# Base_v9.net
KiCad netlist of a schematic drawn in EAGLE
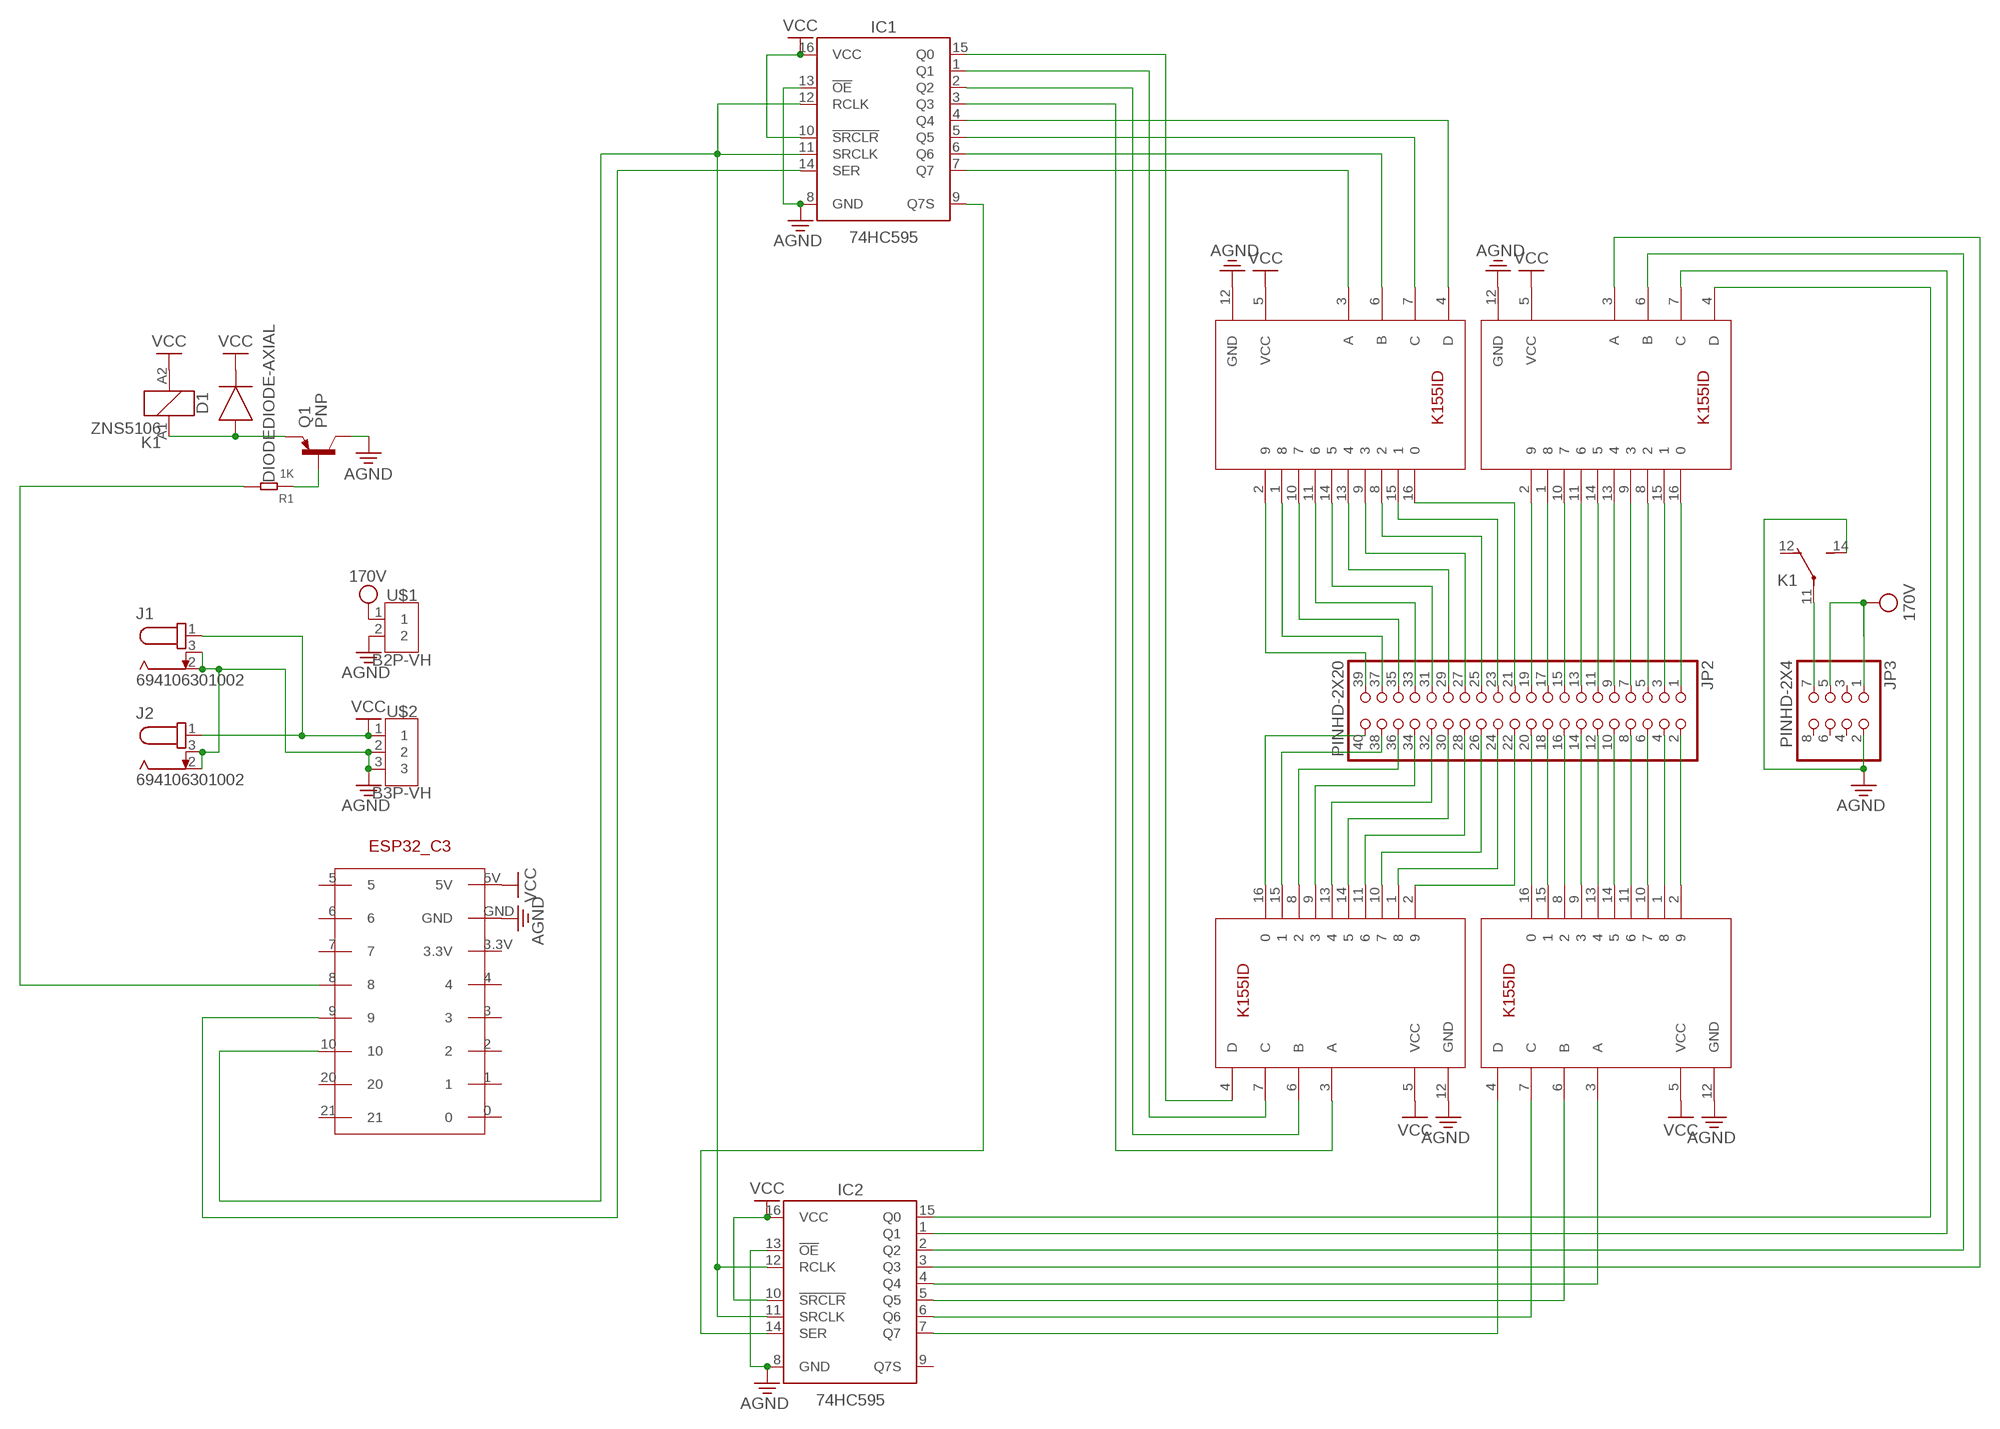
[diagram p0: schematic, sheet 1]

(export (version "E")
  (design (tool "Eeschema 10.0.6"))
  (components
    (comp (ref "D1")
      (value "DIODEDIODE-AXIAL")
      (footprint "eagle-import:DIODE-AXIAL")
      (libsource (lib "eagle-import") (part "DIODEDIODE-AXIAL"))
    )
    (comp (ref "IC1")
      (value "74HC595")
      (footprint "eagle-import:DIP762W53P254L1969H508Q16B")
      (fields (field (name "MANUFACTURER") "Generic"))
      (libsource (lib "eagle-import") (part "74HC595_PDIP"))
    )
    (comp (ref "IC2")
      (value "74HC595")
      (footprint "eagle-import:DIP762W53P254L1969H508Q16B")
      (fields (field (name "MANUFACTURER") "Generic"))
      (libsource (lib "eagle-import") (part "74HC595_PDIP"))
    )
    (comp (ref "IC3")
      (value "K155ID")
      (footprint "eagle-import:K155ID")
      (libsource (lib "eagle-import") (part "K155ID"))
    )
    (comp (ref "IC4")
      (value "K155ID")
      (footprint "eagle-import:K155ID")
      (libsource (lib "eagle-import") (part "K155ID"))
    )
    (comp (ref "IC5")
      (value "K155ID")
      (footprint "eagle-import:K155ID")
      (libsource (lib "eagle-import") (part "K155ID"))
    )
    (comp (ref "IC6")
      (value "K155ID")
      (footprint "eagle-import:K155ID")
      (libsource (lib "eagle-import") (part "K155ID"))
    )
    (comp (ref "J1")
      (value "694106301002")
      (footprint "eagle-import:694106301002")
      (fields
        (field (name "DIGIKEY_PART_NUMBER") "732-5930-ND")
        (field (name "MANUFACTURER") "Wurth Electronics Inc.")
        (field (name "CREATED_BY") "PCBLayout.com")
      )
      (libsource (lib "eagle-import") (part "694106301002"))
    )
    (comp (ref "J2")
      (value "694106301002")
      (footprint "eagle-import:694106301002")
      (fields
        (field (name "DIGIKEY_PART_NUMBER") "732-5930-ND")
        (field (name "MANUFACTURER") "Wurth Electronics Inc.")
        (field (name "CREATED_BY") "PCBLayout.com")
      )
      (libsource (lib "eagle-import") (part "694106301002"))
    )
    (comp (ref "JP2")
      (value "PINHD-2X20")
      (footprint "eagle-import:2X20")
      (fields (field (name "MANUFACTURER") "Generic"))
      (libsource (lib "eagle-import") (part "PINHD-2X20"))
    )
    (comp (ref "JP3")
      (value "PINHD-2X4")
      (footprint "eagle-import:2X04")
      (fields (field (name "MANUFACTURER") "Generic"))
      (libsource (lib "eagle-import") (part "PINHD-2X4"))
    )
    (comp (ref "K1")
      (value "ZNS5106")
      (footprint "eagle-import:ZN5")
      (libsource (lib "eagle-import") (part "ZNS5106"))
    )
    (comp (ref "Q1")
      (value "PNP")
      (footprint "eagle-import:TO92")
      (libsource (lib "eagle-import") (part "PNPTO92-CBE_"))
    )
    (comp (ref "R1")
      (value "1K")
      (footprint "eagle-import:PR-D2.3XL6.5MM")
      (fields (field (name "MPN") "FHCFR-1/4W-102J"))
      (libsource (lib "eagle-import") (part "DIP-RES-1K-5%-1/4W(PR-D2.3XL6.5MM)"))
    )
    (comp (ref "U$1")
      (value "B2P-VH")
      (footprint "eagle-import:B2P-VH_396-2N")
      (fields (field (name "MANUFACTURER") " JST Sales America Inc."))
      (libsource (lib "eagle-import") (part "B2P-VH"))
    )
    (comp (ref "U$2")
      (value "B3P-VH")
      (footprint "eagle-import:B3P-VH_396_3N")
      (fields (field (name "MANUFACTURER") " JST Sales America Inc."))
      (libsource (lib "eagle-import") (part "B3P-VH"))
    )
    (comp (ref "U$5")
      (value "ESP32_C3_SUPERMINI")
      (footprint "eagle-import:ESP32_C3_SUPERMINI")
      (libsource (lib "eagle-import") (part "ESP32_C3_SUPERMINI"))
    )
  )
  (nets
    (net (code "1") (name "170V") (class "Default")
      (node (ref "JP3") (pin "1") (pinfunction "1_1") (pintype "passive"))
      (node (ref "JP3") (pin "5") (pinfunction "5_5") (pintype "passive"))
      (node (ref "U$1") (pin "1") (pinfunction "1_1") (pintype "bidirectional"))
    )
    (net (code "2") (name "AGND") (class "Default")
      (node (ref "IC1") (pin "13") (pinfunction "~{OE}_13") (pintype "output"))
      (node (ref "IC1") (pin "8") (pinfunction "GND_8") (pintype "bidirectional"))
      (node (ref "IC2") (pin "13") (pinfunction "~{OE}_13") (pintype "output"))
      (node (ref "IC2") (pin "8") (pinfunction "GND_8") (pintype "bidirectional"))
      (node (ref "IC3") (pin "12") (pinfunction "GND_12") (pintype "bidirectional"))
      (node (ref "IC4") (pin "12") (pinfunction "GND_12") (pintype "bidirectional"))
      (node (ref "IC5") (pin "12") (pinfunction "GND_12") (pintype "bidirectional"))
      (node (ref "IC6") (pin "12") (pinfunction "GND_12") (pintype "bidirectional"))
      (node (ref "J1") (pin "2") (pinfunction "2_2") (pintype "passive"))
      (node (ref "J1") (pin "3") (pinfunction "3_3") (pintype "passive"))
      (node (ref "J2") (pin "2") (pinfunction "2_2") (pintype "passive"))
      (node (ref "J2") (pin "3") (pinfunction "3_3") (pintype "passive"))
      (node (ref "JP3") (pin "2") (pinfunction "2_2") (pintype "passive"))
      (node (ref "K1") (pin "14") (pinfunction "S_14") (pintype "passive"))
      (node (ref "Q1") (pin "1") (pinfunction "C_1") (pintype "passive"))
      (node (ref "U$1") (pin "2") (pinfunction "2_2") (pintype "bidirectional"))
      (node (ref "U$2") (pin "2") (pinfunction "2_2") (pintype "bidirectional"))
      (node (ref "U$2") (pin "3") (pinfunction "3_3") (pintype "bidirectional"))
      (node (ref "U$5") (pin "GND") (pinfunction "GND_GND") (pintype "bidirectional"))
    )
    (net (code "3") (name "Net-(D1-A)") (class "Default")
      (node (ref "D1") (pin "1") (pinfunction "A_1") (pintype "passive"))
      (node (ref "K1") (pin "A1") (pinfunction "1_A1") (pintype "passive"))
      (node (ref "Q1") (pin "3") (pinfunction "E_3") (pintype "passive"))
    )
    (net (code "4") (name "Net-(IC1-Q0)") (class "Default")
      (node (ref "IC1") (pin "15") (pinfunction "Q0_15") (pintype "output"))
      (node (ref "IC4") (pin "4") (pinfunction "D_4") (pintype "bidirectional"))
    )
    (net (code "5") (name "Net-(IC1-Q1)") (class "Default")
      (node (ref "IC1") (pin "1") (pinfunction "Q1_1") (pintype "output"))
      (node (ref "IC4") (pin "7") (pinfunction "C_7") (pintype "bidirectional"))
    )
    (net (code "6") (name "Net-(IC1-Q2)") (class "Default")
      (node (ref "IC1") (pin "2") (pinfunction "Q2_2") (pintype "output"))
      (node (ref "IC4") (pin "6") (pinfunction "B_6") (pintype "bidirectional"))
    )
    (net (code "7") (name "Net-(IC1-Q3)") (class "Default")
      (node (ref "IC1") (pin "3") (pinfunction "Q3_3") (pintype "output"))
      (node (ref "IC4") (pin "3") (pinfunction "A_3") (pintype "bidirectional"))
    )
    (net (code "8") (name "Net-(IC1-Q4)") (class "Default")
      (node (ref "IC1") (pin "4") (pinfunction "Q4_4") (pintype "output"))
      (node (ref "IC3") (pin "4") (pinfunction "D_4") (pintype "bidirectional"))
    )
    (net (code "9") (name "Net-(IC1-Q5)") (class "Default")
      (node (ref "IC1") (pin "5") (pinfunction "Q5_5") (pintype "output"))
      (node (ref "IC3") (pin "7") (pinfunction "C_7") (pintype "bidirectional"))
    )
    (net (code "10") (name "Net-(IC1-Q6)") (class "Default")
      (node (ref "IC1") (pin "6") (pinfunction "Q6_6") (pintype "output"))
      (node (ref "IC3") (pin "6") (pinfunction "B_6") (pintype "bidirectional"))
    )
    (net (code "11") (name "Net-(IC1-Q7)") (class "Default")
      (node (ref "IC1") (pin "7") (pinfunction "Q7_7") (pintype "output"))
      (node (ref "IC3") (pin "3") (pinfunction "A_3") (pintype "bidirectional"))
    )
    (net (code "12") (name "Net-(IC1-Q7S)") (class "Default")
      (node (ref "IC1") (pin "9") (pinfunction "Q7S_9") (pintype "output"))
      (node (ref "IC2") (pin "14") (pinfunction "SER_14") (pintype "input"))
    )
    (net (code "13") (name "Net-(IC1-RCLK)") (class "Default")
      (node (ref "IC1") (pin "11") (pinfunction "SRCLK_11") (pintype "input"))
      (node (ref "IC1") (pin "12") (pinfunction "RCLK_12") (pintype "input"))
      (node (ref "IC2") (pin "11") (pinfunction "SRCLK_11") (pintype "input"))
      (node (ref "IC2") (pin "12") (pinfunction "RCLK_12") (pintype "input"))
      (node (ref "U$5") (pin "10") (pinfunction "10_10") (pintype "bidirectional"))
    )
    (net (code "14") (name "Net-(IC1-SER)") (class "Default")
      (node (ref "IC1") (pin "14") (pinfunction "SER_14") (pintype "input"))
      (node (ref "U$5") (pin "9") (pinfunction "9_9") (pintype "bidirectional"))
    )
    (net (code "15") (name "Net-(IC2-Q0)") (class "Default")
      (node (ref "IC2") (pin "15") (pinfunction "Q0_15") (pintype "output"))
      (node (ref "IC5") (pin "4") (pinfunction "D_4") (pintype "bidirectional"))
    )
    (net (code "16") (name "Net-(IC2-Q1)") (class "Default")
      (node (ref "IC2") (pin "1") (pinfunction "Q1_1") (pintype "output"))
      (node (ref "IC5") (pin "7") (pinfunction "C_7") (pintype "bidirectional"))
    )
    (net (code "17") (name "Net-(IC2-Q2)") (class "Default")
      (node (ref "IC2") (pin "2") (pinfunction "Q2_2") (pintype "output"))
      (node (ref "IC5") (pin "6") (pinfunction "B_6") (pintype "bidirectional"))
    )
    (net (code "18") (name "Net-(IC2-Q3)") (class "Default")
      (node (ref "IC2") (pin "3") (pinfunction "Q3_3") (pintype "output"))
      (node (ref "IC5") (pin "3") (pinfunction "A_3") (pintype "bidirectional"))
    )
    (net (code "19") (name "Net-(IC2-Q4)") (class "Default")
      (node (ref "IC2") (pin "4") (pinfunction "Q4_4") (pintype "output"))
      (node (ref "IC6") (pin "3") (pinfunction "A_3") (pintype "bidirectional"))
    )
    (net (code "20") (name "Net-(IC2-Q5)") (class "Default")
      (node (ref "IC2") (pin "5") (pinfunction "Q5_5") (pintype "output"))
      (node (ref "IC6") (pin "6") (pinfunction "B_6") (pintype "bidirectional"))
    )
    (net (code "21") (name "Net-(IC2-Q6)") (class "Default")
      (node (ref "IC2") (pin "6") (pinfunction "Q6_6") (pintype "output"))
      (node (ref "IC6") (pin "7") (pinfunction "C_7") (pintype "bidirectional"))
    )
    (net (code "22") (name "Net-(IC2-Q7)") (class "Default")
      (node (ref "IC2") (pin "7") (pinfunction "Q7_7") (pintype "output"))
      (node (ref "IC6") (pin "4") (pinfunction "D_4") (pintype "bidirectional"))
    )
    (net (code "23") (name "Net-(IC3-0)") (class "Default")
      (node (ref "IC3") (pin "16") (pinfunction "0_16") (pintype "bidirectional"))
      (node (ref "JP2") (pin "21") (pinfunction "21_21") (pintype "passive"))
    )
    (net (code "24") (name "Net-(IC3-1)") (class "Default")
      (node (ref "IC3") (pin "15") (pinfunction "1_15") (pintype "bidirectional"))
      (node (ref "JP2") (pin "23") (pinfunction "23_23") (pintype "passive"))
    )
    (net (code "25") (name "Net-(IC3-2)") (class "Default")
      (node (ref "IC3") (pin "8") (pinfunction "2_8") (pintype "bidirectional"))
      (node (ref "JP2") (pin "25") (pinfunction "25_25") (pintype "passive"))
    )
    (net (code "26") (name "Net-(IC3-3)") (class "Default")
      (node (ref "IC3") (pin "9") (pinfunction "3_9") (pintype "bidirectional"))
      (node (ref "JP2") (pin "27") (pinfunction "27_27") (pintype "passive"))
    )
    (net (code "27") (name "Net-(IC3-4)") (class "Default")
      (node (ref "IC3") (pin "13") (pinfunction "4_13") (pintype "bidirectional"))
      (node (ref "JP2") (pin "29") (pinfunction "29_29") (pintype "passive"))
    )
    (net (code "28") (name "Net-(IC3-5)") (class "Default")
      (node (ref "IC3") (pin "14") (pinfunction "5_14") (pintype "bidirectional"))
      (node (ref "JP2") (pin "31") (pinfunction "31_31") (pintype "passive"))
    )
    (net (code "29") (name "Net-(IC3-6)") (class "Default")
      (node (ref "IC3") (pin "11") (pinfunction "6_11") (pintype "bidirectional"))
      (node (ref "JP2") (pin "33") (pinfunction "33_33") (pintype "passive"))
    )
    (net (code "30") (name "Net-(IC3-7)") (class "Default")
      (node (ref "IC3") (pin "10") (pinfunction "7_10") (pintype "bidirectional"))
      (node (ref "JP2") (pin "35") (pinfunction "35_35") (pintype "passive"))
    )
    (net (code "31") (name "Net-(IC3-8)") (class "Default")
      (node (ref "IC3") (pin "1") (pinfunction "8_1") (pintype "bidirectional"))
      (node (ref "JP2") (pin "37") (pinfunction "37_37") (pintype "passive"))
    )
    (net (code "32") (name "Net-(IC3-9)") (class "Default")
      (node (ref "IC3") (pin "2") (pinfunction "9_2") (pintype "bidirectional"))
      (node (ref "JP2") (pin "39") (pinfunction "39_39") (pintype "passive"))
    )
    (net (code "33") (name "Net-(IC4-0)") (class "Default")
      (node (ref "IC4") (pin "16") (pinfunction "0_16") (pintype "bidirectional"))
      (node (ref "JP2") (pin "40") (pinfunction "40_40") (pintype "passive"))
    )
    (net (code "34") (name "Net-(IC4-1)") (class "Default")
      (node (ref "IC4") (pin "15") (pinfunction "1_15") (pintype "bidirectional"))
      (node (ref "JP2") (pin "38") (pinfunction "38_38") (pintype "passive"))
    )
    (net (code "35") (name "Net-(IC4-2)") (class "Default")
      (node (ref "IC4") (pin "8") (pinfunction "2_8") (pintype "bidirectional"))
      (node (ref "JP2") (pin "36") (pinfunction "36_36") (pintype "passive"))
    )
    (net (code "36") (name "Net-(IC4-3)") (class "Default")
      (node (ref "IC4") (pin "9") (pinfunction "3_9") (pintype "bidirectional"))
      (node (ref "JP2") (pin "34") (pinfunction "34_34") (pintype "passive"))
    )
    (net (code "37") (name "Net-(IC4-4)") (class "Default")
      (node (ref "IC4") (pin "13") (pinfunction "4_13") (pintype "bidirectional"))
      (node (ref "JP2") (pin "32") (pinfunction "32_32") (pintype "passive"))
    )
    (net (code "38") (name "Net-(IC4-5)") (class "Default")
      (node (ref "IC4") (pin "14") (pinfunction "5_14") (pintype "bidirectional"))
      (node (ref "JP2") (pin "30") (pinfunction "30_30") (pintype "passive"))
    )
    (net (code "39") (name "Net-(IC4-6)") (class "Default")
      (node (ref "IC4") (pin "11") (pinfunction "6_11") (pintype "bidirectional"))
      (node (ref "JP2") (pin "28") (pinfunction "28_28") (pintype "passive"))
    )
    (net (code "40") (name "Net-(IC4-7)") (class "Default")
      (node (ref "IC4") (pin "10") (pinfunction "7_10") (pintype "bidirectional"))
      (node (ref "JP2") (pin "26") (pinfunction "26_26") (pintype "passive"))
    )
    (net (code "41") (name "Net-(IC4-8)") (class "Default")
      (node (ref "IC4") (pin "1") (pinfunction "8_1") (pintype "bidirectional"))
      (node (ref "JP2") (pin "24") (pinfunction "24_24") (pintype "passive"))
    )
    (net (code "42") (name "Net-(IC4-9)") (class "Default")
      (node (ref "IC4") (pin "2") (pinfunction "9_2") (pintype "bidirectional"))
      (node (ref "JP2") (pin "22") (pinfunction "22_22") (pintype "passive"))
    )
    (net (code "43") (name "Net-(IC5-0)") (class "Default")
      (node (ref "IC5") (pin "16") (pinfunction "0_16") (pintype "bidirectional"))
      (node (ref "JP2") (pin "1") (pinfunction "1_1") (pintype "passive"))
    )
    (net (code "44") (name "Net-(IC5-1)") (class "Default")
      (node (ref "IC5") (pin "15") (pinfunction "1_15") (pintype "bidirectional"))
      (node (ref "JP2") (pin "3") (pinfunction "3_3") (pintype "passive"))
    )
    (net (code "45") (name "Net-(IC5-2)") (class "Default")
      (node (ref "IC5") (pin "8") (pinfunction "2_8") (pintype "bidirectional"))
      (node (ref "JP2") (pin "5") (pinfunction "5_5") (pintype "passive"))
    )
    (net (code "46") (name "Net-(IC5-3)") (class "Default")
      (node (ref "IC5") (pin "9") (pinfunction "3_9") (pintype "bidirectional"))
      (node (ref "JP2") (pin "7") (pinfunction "7_7") (pintype "passive"))
    )
    (net (code "47") (name "Net-(IC5-4)") (class "Default")
      (node (ref "IC5") (pin "13") (pinfunction "4_13") (pintype "bidirectional"))
      (node (ref "JP2") (pin "9") (pinfunction "9_9") (pintype "passive"))
    )
    (net (code "48") (name "Net-(IC5-5)") (class "Default")
      (node (ref "IC5") (pin "14") (pinfunction "5_14") (pintype "bidirectional"))
      (node (ref "JP2") (pin "11") (pinfunction "11_11") (pintype "passive"))
    )
    (net (code "49") (name "Net-(IC5-6)") (class "Default")
      (node (ref "IC5") (pin "11") (pinfunction "6_11") (pintype "bidirectional"))
      (node (ref "JP2") (pin "13") (pinfunction "13_13") (pintype "passive"))
    )
    (net (code "50") (name "Net-(IC5-7)") (class "Default")
      (node (ref "IC5") (pin "10") (pinfunction "7_10") (pintype "bidirectional"))
      (node (ref "JP2") (pin "15") (pinfunction "15_15") (pintype "passive"))
    )
    (net (code "51") (name "Net-(IC5-8)") (class "Default")
      (node (ref "IC5") (pin "1") (pinfunction "8_1") (pintype "bidirectional"))
      (node (ref "JP2") (pin "17") (pinfunction "17_17") (pintype "passive"))
    )
    (net (code "52") (name "Net-(IC5-9)") (class "Default")
      (node (ref "IC5") (pin "2") (pinfunction "9_2") (pintype "bidirectional"))
      (node (ref "JP2") (pin "19") (pinfunction "19_19") (pintype "passive"))
    )
    (net (code "53") (name "Net-(IC6-0)") (class "Default")
      (node (ref "IC6") (pin "16") (pinfunction "0_16") (pintype "bidirectional"))
      (node (ref "JP2") (pin "20") (pinfunction "20_20") (pintype "passive"))
    )
    (net (code "54") (name "Net-(IC6-1)") (class "Default")
      (node (ref "IC6") (pin "15") (pinfunction "1_15") (pintype "bidirectional"))
      (node (ref "JP2") (pin "18") (pinfunction "18_18") (pintype "passive"))
    )
    (net (code "55") (name "Net-(IC6-2)") (class "Default")
      (node (ref "IC6") (pin "8") (pinfunction "2_8") (pintype "bidirectional"))
      (node (ref "JP2") (pin "16") (pinfunction "16_16") (pintype "passive"))
    )
    (net (code "56") (name "Net-(IC6-3)") (class "Default")
      (node (ref "IC6") (pin "9") (pinfunction "3_9") (pintype "bidirectional"))
      (node (ref "JP2") (pin "14") (pinfunction "14_14") (pintype "passive"))
    )
    (net (code "57") (name "Net-(IC6-4)") (class "Default")
      (node (ref "IC6") (pin "13") (pinfunction "4_13") (pintype "bidirectional"))
      (node (ref "JP2") (pin "12") (pinfunction "12_12") (pintype "passive"))
    )
    (net (code "58") (name "Net-(IC6-5)") (class "Default")
      (node (ref "IC6") (pin "14") (pinfunction "5_14") (pintype "bidirectional"))
      (node (ref "JP2") (pin "10") (pinfunction "10_10") (pintype "passive"))
    )
    (net (code "59") (name "Net-(IC6-6)") (class "Default")
      (node (ref "IC6") (pin "11") (pinfunction "6_11") (pintype "bidirectional"))
      (node (ref "JP2") (pin "8") (pinfunction "8_8") (pintype "passive"))
    )
    (net (code "60") (name "Net-(IC6-7)") (class "Default")
      (node (ref "IC6") (pin "10") (pinfunction "7_10") (pintype "bidirectional"))
      (node (ref "JP2") (pin "6") (pinfunction "6_6") (pintype "passive"))
    )
    (net (code "61") (name "Net-(IC6-8)") (class "Default")
      (node (ref "IC6") (pin "1") (pinfunction "8_1") (pintype "bidirectional"))
      (node (ref "JP2") (pin "4") (pinfunction "4_4") (pintype "passive"))
    )
    (net (code "62") (name "Net-(IC6-9)") (class "Default")
      (node (ref "IC6") (pin "2") (pinfunction "9_2") (pintype "bidirectional"))
      (node (ref "JP2") (pin "2") (pinfunction "2_2") (pintype "passive"))
    )
    (net (code "63") (name "Net-(K1B-P)") (class "Default")
      (node (ref "JP3") (pin "7") (pinfunction "7_7") (pintype "passive"))
      (node (ref "K1") (pin "11") (pinfunction "P_11") (pintype "passive"))
    )
    (net (code "64") (name "Net-(Q1-B)") (class "Default")
      (node (ref "Q1") (pin "2") (pinfunction "B_2") (pintype "passive"))
      (node (ref "R1") (pin "1") (pinfunction "1_1") (pintype "passive"))
    )
    (net (code "65") (name "Net-(R1-Pad2)") (class "Default")
      (node (ref "R1") (pin "2") (pinfunction "2_2") (pintype "passive"))
      (node (ref "U$5") (pin "8") (pinfunction "8_8") (pintype "bidirectional"))
    )
    (net (code "66") (name "VCC") (class "Default")
      (node (ref "D1") (pin "2") (pinfunction "C_2") (pintype "passive"))
      (node (ref "IC1") (pin "10") (pinfunction "~{SRCLR}_10") (pintype "input"))
      (node (ref "IC1") (pin "16") (pinfunction "VCC_16") (pintype "bidirectional"))
      (node (ref "IC2") (pin "10") (pinfunction "~{SRCLR}_10") (pintype "input"))
      (node (ref "IC2") (pin "16") (pinfunction "VCC_16") (pintype "bidirectional"))
      (node (ref "IC3") (pin "5") (pinfunction "VCC_5") (pintype "bidirectional"))
      (node (ref "IC4") (pin "5") (pinfunction "VCC_5") (pintype "bidirectional"))
      (node (ref "IC5") (pin "5") (pinfunction "VCC_5") (pintype "bidirectional"))
      (node (ref "IC6") (pin "5") (pinfunction "VCC_5") (pintype "bidirectional"))
      (node (ref "J1") (pin "1") (pinfunction "1_1") (pintype "passive"))
      (node (ref "J2") (pin "1") (pinfunction "1_1") (pintype "passive"))
      (node (ref "K1") (pin "A2") (pinfunction "2_A2") (pintype "passive"))
      (node (ref "U$2") (pin "1") (pinfunction "1_1") (pintype "bidirectional"))
      (node (ref "U$5") (pin "5V") (pinfunction "5V_5V") (pintype "bidirectional"))
    )
    (net (code "67") (name "unconnected-(IC2-Q7S-Pad9)") (class "Default")
      (node (ref "IC2") (pin "9") (pinfunction "Q7S_9") (pintype "output"))
    )
    (net (code "68") (name "unconnected-(JP3-Pad3)") (class "Default")
      (node (ref "JP3") (pin "3") (pinfunction "3_3") (pintype "passive"))
    )
    (net (code "69") (name "unconnected-(JP3-Pad4)") (class "Default")
      (node (ref "JP3") (pin "4") (pinfunction "4_4") (pintype "passive"))
    )
    (net (code "70") (name "unconnected-(JP3-Pad6)") (class "Default")
      (node (ref "JP3") (pin "6") (pinfunction "6_6") (pintype "passive"))
    )
    (net (code "71") (name "unconnected-(JP3-Pad8)") (class "Default")
      (node (ref "JP3") (pin "8") (pinfunction "8_8") (pintype "passive"))
    )
    (net (code "72") (name "unconnected-(K1B-O-Pad12)") (class "Default")
      (node (ref "K1") (pin "12") (pinfunction "O_12") (pintype "passive"))
    )
    (net (code "73") (name "unconnected-(U$5-Pad0)") (class "Default")
      (node (ref "U$5") (pin "0") (pinfunction "0_0") (pintype "bidirectional"))
    )
    (net (code "74") (name "unconnected-(U$5-Pad1)") (class "Default")
      (node (ref "U$5") (pin "1") (pinfunction "1_1") (pintype "bidirectional"))
    )
    (net (code "75") (name "unconnected-(U$5-Pad2)") (class "Default")
      (node (ref "U$5") (pin "2") (pinfunction "2_2") (pintype "bidirectional"))
    )
    (net (code "76") (name "unconnected-(U$5-Pad3)") (class "Default")
      (node (ref "U$5") (pin "3") (pinfunction "3_3") (pintype "bidirectional"))
    )
    (net (code "77") (name "unconnected-(U$5-Pad3.3V)") (class "Default")
      (node (ref "U$5") (pin "3.3V") (pinfunction "3.3V_3.3V") (pintype "bidirectional"))
    )
    (net (code "78") (name "unconnected-(U$5-Pad4)") (class "Default")
      (node (ref "U$5") (pin "4") (pinfunction "4_4") (pintype "bidirectional"))
    )
    (net (code "79") (name "unconnected-(U$5-Pad5)") (class "Default")
      (node (ref "U$5") (pin "5") (pinfunction "5_5") (pintype "bidirectional"))
    )
    (net (code "80") (name "unconnected-(U$5-Pad6)") (class "Default")
      (node (ref "U$5") (pin "6") (pinfunction "6_6") (pintype "bidirectional"))
    )
    (net (code "81") (name "unconnected-(U$5-Pad7)") (class "Default")
      (node (ref "U$5") (pin "7") (pinfunction "7_7") (pintype "bidirectional"))
    )
    (net (code "82") (name "unconnected-(U$5-Pad20)") (class "Default")
      (node (ref "U$5") (pin "20") (pinfunction "20_20") (pintype "bidirectional"))
    )
    (net (code "83") (name "unconnected-(U$5-Pad21)") (class "Default")
      (node (ref "U$5") (pin "21") (pinfunction "21_21") (pintype "bidirectional"))
    )
  )
)
